# CATS-Vega-PM.net
KiCad netlist of a schematic drawn in Altium Designer
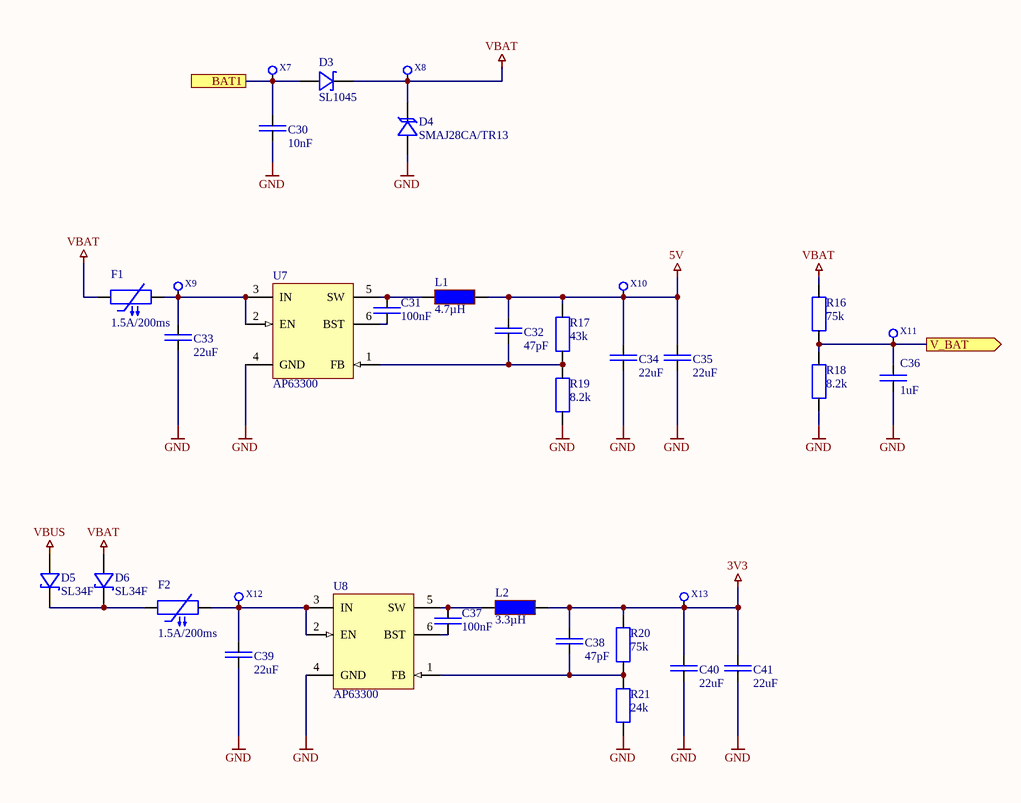
[diagram p0: CATS-Vega-PM.SchDoc]

(export (version "E")
  (design (tool "Eeschema 10.0.6"))
  (components
    (comp (ref "C30")
      (value "10nF")
      (footprint "SMD Keramikkondensator 0603")
      (description "SMD Ceramic Capacitor E6")
      (libsource (lib "CATS-EUROC") (part "E6 - 10nF"))
    )
    (comp (ref "C31")
      (value "100nF")
      (footprint "SMD Keramikkondensator 0603")
      (description "SMD Ceramic Capacitor E6")
      (libsource (lib "Ceramic Capacitors-E6") (part "E6 - 100nF"))
    )
    (comp (ref "C32")
      (value "47pF")
      (footprint "SMD Keramikkondensator 0603")
      (description "SMD Ceramic Capacitor E6")
      (libsource (lib "Ceramic Capacitors-E6") (part "E6 - 47pF"))
    )
    (comp (ref "C33")
      (value "22uF")
      (footprint "SMD Keramikkondensator 0805")
      (description "SMD Ceramic Capacitor E6")
      (libsource (lib "Ceramic Capacitors-E6") (part "E6 - 22uF"))
    )
    (comp (ref "C34")
      (value "22uF")
      (footprint "SMD Keramikkondensator 0805")
      (description "SMD Ceramic Capacitor E6")
      (libsource (lib "Ceramic Capacitors-E6") (part "E6 - 22uF"))
    )
    (comp (ref "C35")
      (value "22uF")
      (footprint "SMD Keramikkondensator 0805")
      (description "SMD Ceramic Capacitor E6")
      (libsource (lib "Ceramic Capacitors-E6") (part "E6 - 22uF"))
    )
    (comp (ref "C36")
      (value "1uF")
      (footprint "SMD Keramikkondensator 0603")
      (description "SMD Ceramic Capacitor E6")
      (libsource (lib "CATS-EUROC") (part "E6 - 1uF"))
    )
    (comp (ref "C37")
      (value "100nF")
      (footprint "SMD Keramikkondensator 0603")
      (description "SMD Ceramic Capacitor E6")
      (libsource (lib "Ceramic Capacitors-E6") (part "E6 - 100nF"))
    )
    (comp (ref "C38")
      (value "47pF")
      (footprint "SMD Keramikkondensator 0603")
      (description "SMD Ceramic Capacitor E6")
      (libsource (lib "Ceramic Capacitors-E6") (part "E6 - 47pF"))
    )
    (comp (ref "C39")
      (value "22uF")
      (footprint "SMD Keramikkondensator 0805")
      (description "SMD Ceramic Capacitor E6")
      (libsource (lib "CATS-EUROC") (part "E6 - 22uF"))
    )
    (comp (ref "C40")
      (value "22uF")
      (footprint "SMD Keramikkondensator 0805")
      (description "SMD Ceramic Capacitor E6")
      (libsource (lib "Ceramic Capacitors-E6") (part "E6 - 22uF"))
    )
    (comp (ref "C41")
      (value "22uF")
      (footprint "SMD Keramikkondensator 0805")
      (description "SMD Ceramic Capacitor E6")
      (libsource (lib "Ceramic Capacitors-E6") (part "E6 - 22uF"))
    )
    (comp (ref "D3")
      (value "SL1045")
      (footprint "SMD Diode TO-277")
      (description "45V 470mV@10A 10A TO-277 Schottky Barrier Diodes")
      (libsource (lib "Diodes") (part "SL1045"))
    )
    (comp (ref "D4")
      (value "SMAJ28CA/TR13")
      (footprint "SMD Diode DO-214-AC (SMA)")
      (description "TVS Diode, 31.10~34.40V Breakdown, 8.8A Pulse")
      (libsource (lib "Diodes") (part "SMAJ28CA/TR13"))
    )
    (comp (ref "D5")
      (value "SL34F")
      (footprint "SMD Diode SMAF")
      (description "3A SMAF Schottky Barrier Diode")
      (libsource (lib "Diodes") (part "SL34F"))
    )
    (comp (ref "D6")
      (value "SL34F")
      (footprint "SMD Diode SMAF")
      (description "3A SMAF Schottky Barrier Diode")
      (libsource (lib "Diodes") (part "SL34F"))
    )
    (comp (ref "F1")
      (value "1.5A/200ms")
      (footprint "SMD PPTC-Fuse 1206")
      (description "Polymeric PTC Resettable Fuse 30V 0.75A Surface Mount 1206")
      (libsource (lib "Other") (part "ASMD1206-075-30V"))
    )
    (comp (ref "F2")
      (value "1.5A/200ms")
      (footprint "SMD PPTC-Fuse 1206")
      (description "Polymeric PTC Resettable Fuse 30V 0.75A Surface Mount 1206")
      (libsource (lib "Other") (part "ASMD1206-075-30V"))
    )
    (comp (ref "L1")
      (value "4.7µH")
      (footprint "SMD Inductor 5.5x5.2x3")
      (description "4.7 µH Shielded Molded Inductor 4.5 A 60mOhm Max Nonstandard")
      (libsource (lib "Inductors") (part "Inductor 4.7µH / 4.5A"))
    )
    (comp (ref "L2")
      (value "3.3µH")
      (footprint "SMD Inductor 2x2.5x1.2")
      (description "1.15A 3.3uH ±20% 144mΩ SMD Power Inductors")
      (libsource (lib "Inductors") (part "Inductor 3.3µH / 1.15A"))
    )
    (comp (ref "R16")
      (value "75k")
      (footprint "SMD Widerstand 0603")
      (description "SMD Chip Resistor E24")
      (libsource (lib "Resistors-E24") (part "E24 - 75k"))
    )
    (comp (ref "R17")
      (value "43k")
      (footprint "SMD Widerstand 0603")
      (description "SMD Chip Resistor E24")
      (libsource (lib "Resistors-E24") (part "E24 - 43k"))
    )
    (comp (ref "R18")
      (value "8.2k")
      (footprint "SMD Widerstand 0603")
      (description "SMD Chip Resistor E24")
      (libsource (lib "Resistors-E24") (part "E24 - 8.2k"))
    )
    (comp (ref "R19")
      (value "8.2k")
      (footprint "SMD Widerstand 0603")
      (description "SMD Chip Resistor E24")
      (libsource (lib "Resistors-E24") (part "E24 - 8.2k"))
    )
    (comp (ref "R20")
      (value "75k")
      (footprint "SMD Widerstand 0603")
      (description "SMD Chip Resistor E24")
      (libsource (lib "Resistors-E24") (part "E24 - 75k"))
    )
    (comp (ref "R21")
      (value "24k")
      (footprint "SMD Widerstand 0603")
      (description "SMD Chip Resistor E24")
      (libsource (lib "Resistors-E24") (part "E24 - 24k"))
    )
    (comp (ref "U7")
      (value "AP63300")
      (footprint "SMD IC TSOT-23-6")
      (description "3.8V TO 32V INPUT, 3A LOW IQ SYNCHRONOUS BUCK WITH ENHANCED EMI REDUCTION")
      (libsource (lib "Voltage-Converter") (part "AP63300"))
    )
    (comp (ref "U8")
      (value "AP63300")
      (footprint "SMD IC TSOT-23-6")
      (description "3.8V TO 32V INPUT, 3A LOW IQ SYNCHRONOUS BUCK WITH ENHANCED EMI REDUCTION")
      (libsource (lib "Voltage-Converter") (part "AP63300"))
    )
    (comp (ref "X7")
      (value "-")
      (footprint "SMD Test point 0.8mm")
      (description "Test Point SMD")
      (libsource (lib "Connectors") (part "SMD Test point"))
    )
    (comp (ref "X8")
      (value "-")
      (footprint "SMD Test point 0.8mm")
      (description "Test Point SMD")
      (libsource (lib "Connectors") (part "SMD Test point"))
    )
    (comp (ref "X9")
      (value "-")
      (footprint "SMD Test point 0.8mm")
      (description "Test Point SMD")
      (libsource (lib "Connectors") (part "SMD Test point"))
    )
    (comp (ref "X10")
      (value "-")
      (footprint "SMD Test point 0.8mm")
      (description "Test Point SMD")
      (libsource (lib "Connectors") (part "SMD Test point"))
    )
    (comp (ref "X11")
      (value "-")
      (footprint "SMD Test point 0.8mm")
      (description "Test Point SMD")
      (libsource (lib "Connectors") (part "SMD Test point"))
    )
    (comp (ref "X12")
      (value "-")
      (footprint "SMD Test point 0.8mm")
      (description "Test Point SMD")
      (libsource (lib "Connectors") (part "SMD Test point"))
    )
    (comp (ref "X13")
      (value "-")
      (footprint "SMD Test point 0.8mm")
      (description "Test Point SMD")
      (libsource (lib "Connectors") (part "SMD Test point"))
    )
  )
  (nets
    (net (code "1") (name "/BAT1") (class "Default")
      (node (ref "C30") (pin "2") (pinfunction "2_2") (pintype "passive"))
      (node (ref "D3") (pin "A") (pinfunction "A_A") (pintype "passive"))
      (node (ref "X7") (pin "1") (pinfunction "1_1") (pintype "passive"))
    )
    (net (code "2") (name "/V_BAT") (class "Default")
      (node (ref "C36") (pin "2") (pinfunction "2_2") (pintype "passive"))
      (node (ref "R16") (pin "1") (pinfunction "1_1") (pintype "passive"))
      (node (ref "R18") (pin "2") (pinfunction "2_2") (pintype "passive"))
      (node (ref "X11") (pin "1") (pinfunction "1_1") (pintype "passive"))
    )
    (net (code "3") (name "3V3") (class "Default")
      (node (ref "C38") (pin "2") (pinfunction "2_2") (pintype "passive"))
      (node (ref "C40") (pin "2") (pinfunction "2_2") (pintype "passive"))
      (node (ref "C41") (pin "2") (pinfunction "2_2") (pintype "passive"))
      (node (ref "L2") (pin "2") (pinfunction "2_2") (pintype "passive"))
      (node (ref "R20") (pin "2") (pinfunction "2_2") (pintype "passive"))
      (node (ref "X13") (pin "1") (pinfunction "1_1") (pintype "passive"))
    )
    (net (code "4") (name "5V") (class "Default")
      (node (ref "C32") (pin "2") (pinfunction "2_2") (pintype "passive"))
      (node (ref "C34") (pin "2") (pinfunction "2_2") (pintype "passive"))
      (node (ref "C35") (pin "2") (pinfunction "2_2") (pintype "passive"))
      (node (ref "L1") (pin "2") (pinfunction "2_2") (pintype "passive"))
      (node (ref "R17") (pin "2") (pinfunction "2_2") (pintype "passive"))
      (node (ref "X10") (pin "1") (pinfunction "1_1") (pintype "passive"))
    )
    (net (code "5") (name "GND") (class "Default")
      (node (ref "C30") (pin "1") (pinfunction "1_1") (pintype "passive"))
      (node (ref "C33") (pin "1") (pinfunction "1_1") (pintype "passive"))
      (node (ref "C34") (pin "1") (pinfunction "1_1") (pintype "passive"))
      (node (ref "C35") (pin "1") (pinfunction "1_1") (pintype "passive"))
      (node (ref "C36") (pin "1") (pinfunction "1_1") (pintype "passive"))
      (node (ref "C39") (pin "1") (pinfunction "1_1") (pintype "passive"))
      (node (ref "C40") (pin "1") (pinfunction "1_1") (pintype "passive"))
      (node (ref "C41") (pin "1") (pinfunction "1_1") (pintype "passive"))
      (node (ref "D4") (pin "A") (pinfunction "A_A") (pintype "passive"))
      (node (ref "R18") (pin "1") (pinfunction "1_1") (pintype "passive"))
      (node (ref "R19") (pin "1") (pinfunction "1_1") (pintype "passive"))
      (node (ref "R21") (pin "1") (pinfunction "1_1") (pintype "passive"))
      (node (ref "U7") (pin "4") (pinfunction "GND_4") (pintype "passive"))
      (node (ref "U8") (pin "4") (pinfunction "GND_4") (pintype "passive"))
    )
    (net (code "6") (name "Net-(D5-PadK)") (class "Default")
      (node (ref "D5") (pin "K") (pinfunction "K_K") (pintype "passive"))
      (node (ref "D6") (pin "K") (pinfunction "K_K") (pintype "passive"))
      (node (ref "F2") (pin "2") (pinfunction "2_2") (pintype "passive"))
    )
    (net (code "7") (name "Net-(U7-BST)") (class "Default")
      (node (ref "C31") (pin "1") (pinfunction "1_1") (pintype "passive"))
      (node (ref "U7") (pin "6") (pinfunction "BST_6") (pintype "passive"))
    )
    (net (code "8") (name "Net-(U7-EN)") (class "Default")
      (node (ref "C33") (pin "2") (pinfunction "2_2") (pintype "passive"))
      (node (ref "F1") (pin "1") (pinfunction "1_1") (pintype "passive"))
      (node (ref "U7") (pin "2") (pinfunction "EN_2") (pintype "input"))
      (node (ref "U7") (pin "3") (pinfunction "IN_3") (pintype "passive"))
      (node (ref "X9") (pin "1") (pinfunction "1_1") (pintype "passive"))
    )
    (net (code "9") (name "Net-(U7-FB)") (class "Default")
      (node (ref "C32") (pin "1") (pinfunction "1_1") (pintype "passive"))
      (node (ref "R17") (pin "1") (pinfunction "1_1") (pintype "passive"))
      (node (ref "R19") (pin "2") (pinfunction "2_2") (pintype "passive"))
      (node (ref "U7") (pin "1") (pinfunction "FB_1") (pintype "input"))
    )
    (net (code "10") (name "Net-(U7-SW)") (class "Default")
      (node (ref "C31") (pin "2") (pinfunction "2_2") (pintype "passive"))
      (node (ref "L1") (pin "1") (pinfunction "1_1") (pintype "passive"))
      (node (ref "U7") (pin "5") (pinfunction "SW_5") (pintype "passive"))
    )
    (net (code "11") (name "Net-(U8-BST)") (class "Default")
      (node (ref "C37") (pin "1") (pinfunction "1_1") (pintype "passive"))
      (node (ref "U8") (pin "6") (pinfunction "BST_6") (pintype "passive"))
    )
    (net (code "12") (name "Net-(U8-EN)") (class "Default")
      (node (ref "C39") (pin "2") (pinfunction "2_2") (pintype "passive"))
      (node (ref "F2") (pin "1") (pinfunction "1_1") (pintype "passive"))
      (node (ref "U8") (pin "2") (pinfunction "EN_2") (pintype "input"))
      (node (ref "U8") (pin "3") (pinfunction "IN_3") (pintype "passive"))
      (node (ref "X12") (pin "1") (pinfunction "1_1") (pintype "passive"))
    )
    (net (code "13") (name "Net-(U8-FB)") (class "Default")
      (node (ref "C38") (pin "1") (pinfunction "1_1") (pintype "passive"))
      (node (ref "R20") (pin "1") (pinfunction "1_1") (pintype "passive"))
      (node (ref "R21") (pin "2") (pinfunction "2_2") (pintype "passive"))
      (node (ref "U8") (pin "1") (pinfunction "FB_1") (pintype "input"))
    )
    (net (code "14") (name "Net-(U8-SW)") (class "Default")
      (node (ref "C37") (pin "2") (pinfunction "2_2") (pintype "passive"))
      (node (ref "L2") (pin "1") (pinfunction "1_1") (pintype "passive"))
      (node (ref "U8") (pin "5") (pinfunction "SW_5") (pintype "passive"))
    )
    (net (code "15") (name "VBAT") (class "Default")
      (node (ref "D3") (pin "K") (pinfunction "K_K") (pintype "passive"))
      (node (ref "D4") (pin "K") (pinfunction "K_K") (pintype "passive"))
      (node (ref "D6") (pin "A") (pinfunction "A_A") (pintype "passive"))
      (node (ref "F1") (pin "2") (pinfunction "2_2") (pintype "passive"))
      (node (ref "R16") (pin "2") (pinfunction "2_2") (pintype "passive"))
      (node (ref "X8") (pin "1") (pinfunction "1_1") (pintype "passive"))
    )
    (net (code "16") (name "VBUS") (class "Default")
      (node (ref "D5") (pin "A") (pinfunction "A_A") (pintype "passive"))
    )
  )
)
